# Voltage_Battery_Measure.net
KiCad netlist of a schematic drawn in Altium Designer
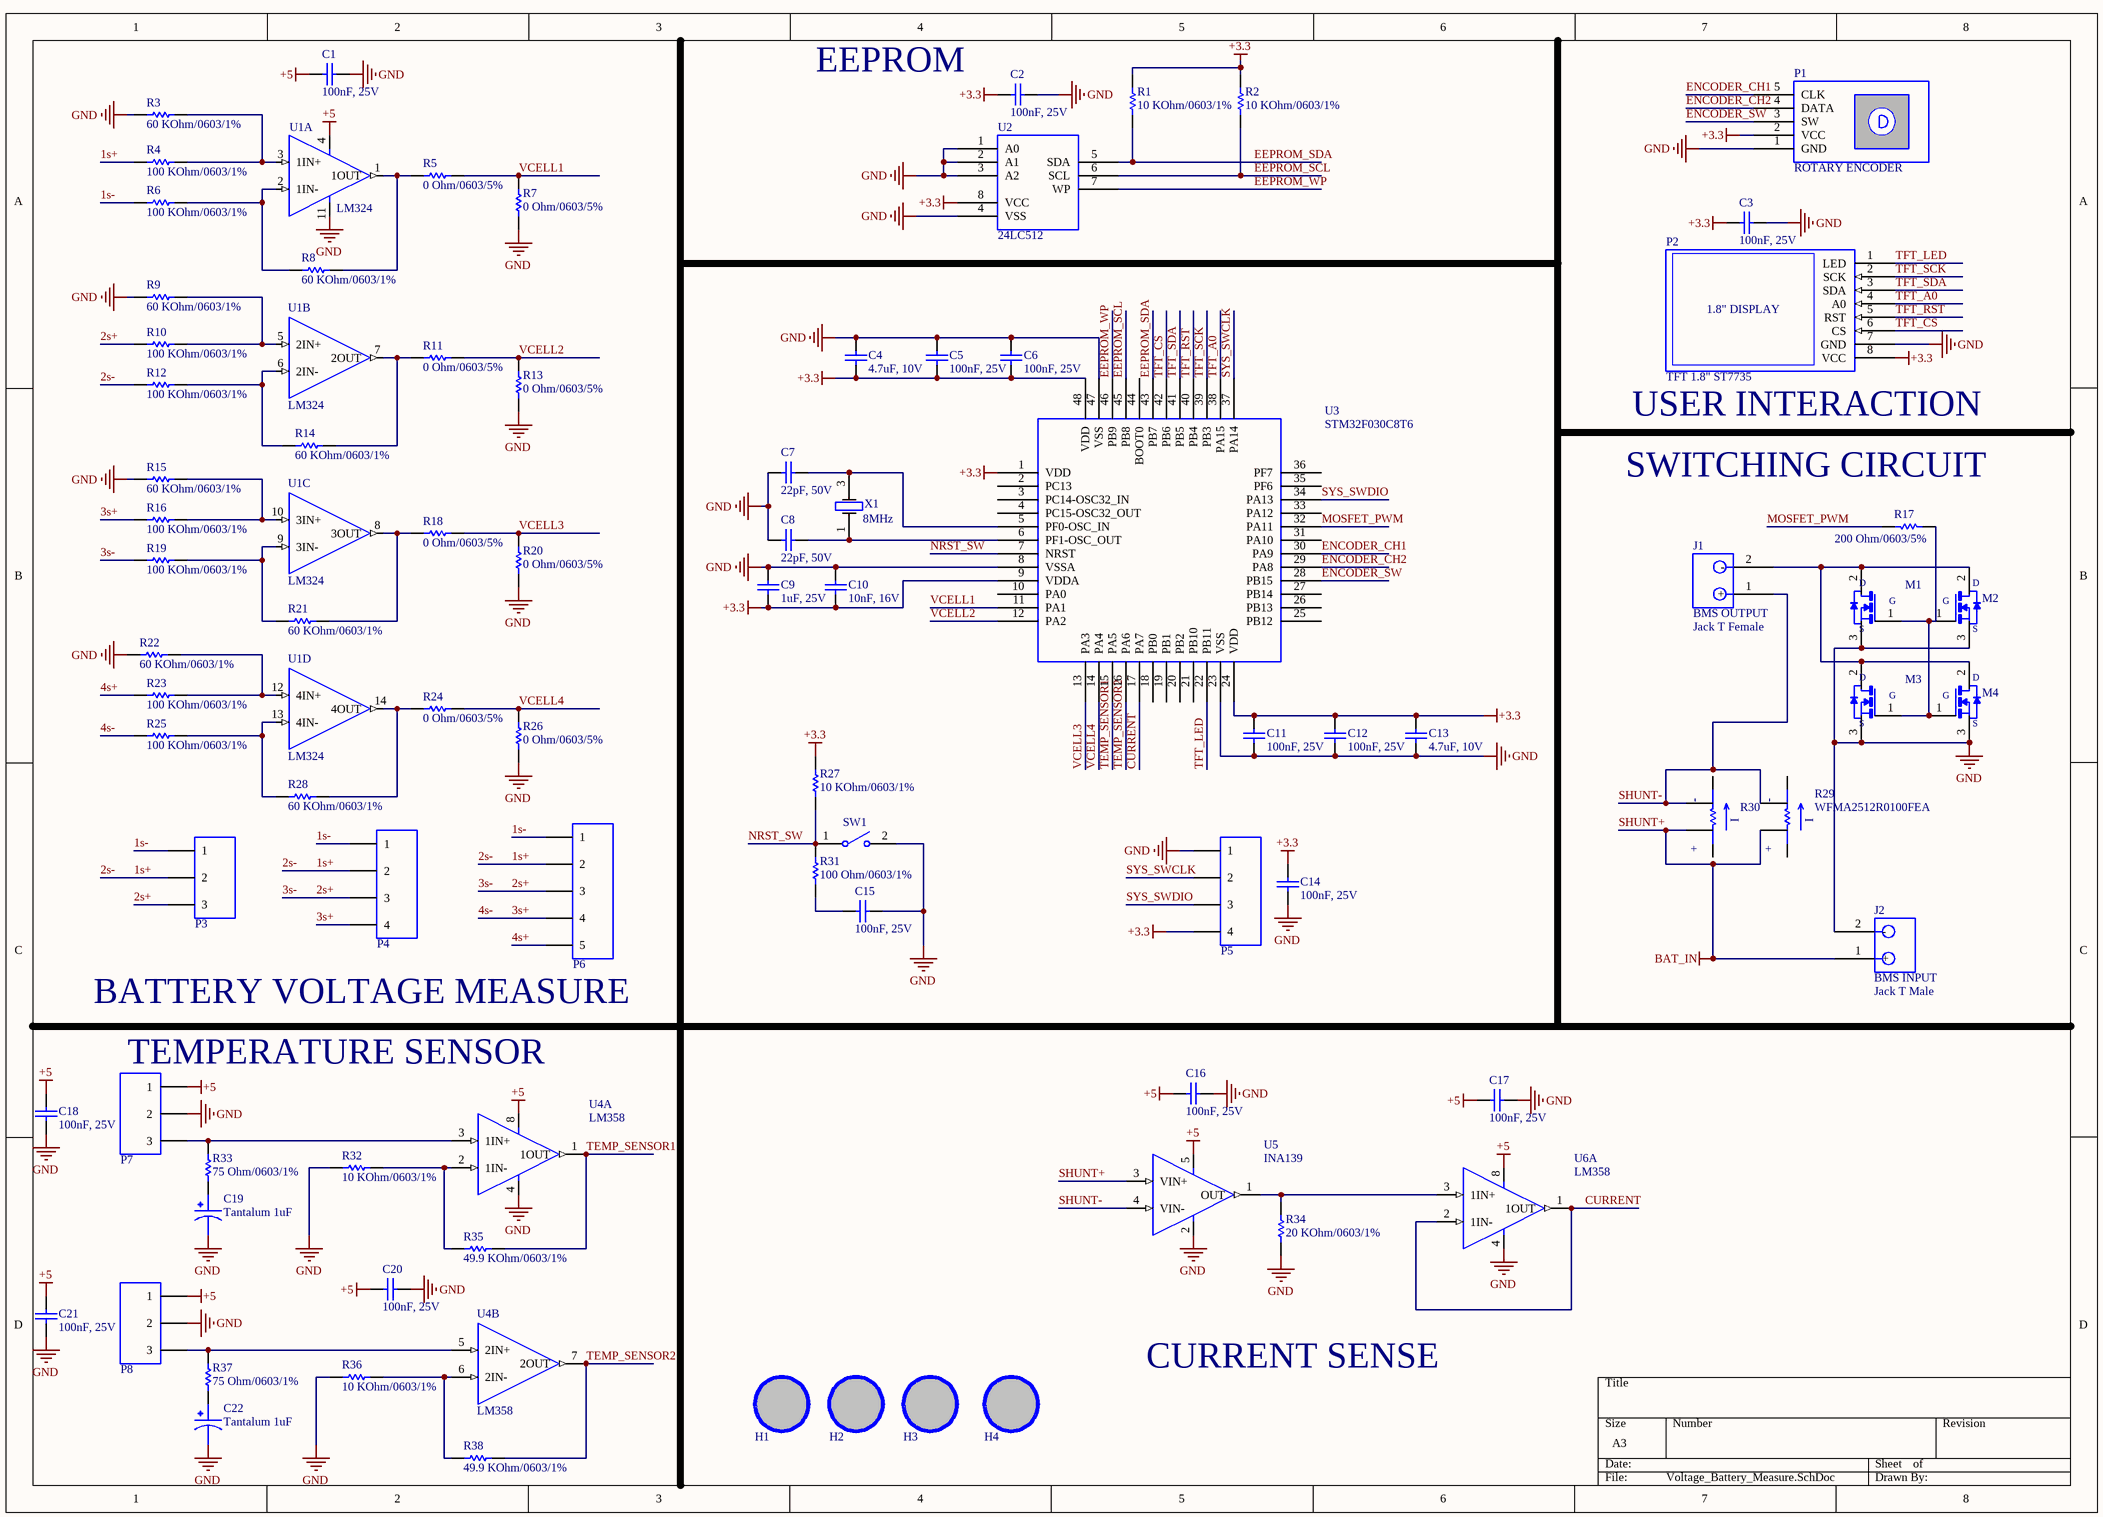
[diagram p0: Voltage_Battery_Measure.SchDoc]

(export (version "E")
  (design (tool "Eeschema 10.0.6"))
  (components
    (comp (ref "C1")
      (value "100nF, 25V")
      (footprint "WCAP-CSGP_0603_H=0.8mm_Reflow")
      (description "WCAP-CSGP Multilayer Ceramic Chip Capacitor, General Purpose, size 0603, X7R, 100nF, 25V")
      (fields
        (field (name "MANUFACTURER PART NUMBER") "885012206071")
        (field (name "MANUFACTURER") "Wurth Elektronik")
      )
      (libsource (lib "Altium_WCAP-CSGP (rev20a)") (part "885012206071"))
    )
    (comp (ref "C2")
      (value "100nF, 25V")
      (footprint "WCAP-CSGP_0603_H=0.8mm_Reflow")
      (description "WCAP-CSGP Multilayer Ceramic Chip Capacitor, General Purpose, size 0603, X7R, 100nF, 25V")
      (fields
        (field (name "MANUFACTURER PART NUMBER") "885012206071")
        (field (name "MANUFACTURER") "Wurth Elektronik")
      )
      (libsource (lib "Altium_WCAP-CSGP (rev20a)") (part "885012206071"))
    )
    (comp (ref "C3")
      (value "100nF, 25V")
      (footprint "WCAP-CSGP_0603_H=0.8mm_Reflow")
      (description "WCAP-CSGP Multilayer Ceramic Chip Capacitor, General Purpose, size 0603, X7R, 100nF, 25V")
      (fields
        (field (name "MANUFACTURER PART NUMBER") "885012206071")
        (field (name "MANUFACTURER") "Wurth Elektronik")
      )
      (libsource (lib "Altium_WCAP-CSGP (rev20a)") (part "885012206071"))
    )
    (comp (ref "C4")
      (value "4.7uF, 10V")
      (footprint "WCAP-CSGP_0603_H=0.8mm_Reflow")
      (description "WCAP-CSGP Multilayer Ceramic Chip Capacitor, General Purpose, size 0603, X5R, 4.7uF, 10V")
      (fields
        (field (name "MANUFACTURER PART NUMBER") "885012106012")
        (field (name "MANUFACTURER") "Wurth Elektronik")
      )
      (libsource (lib "Altium_WCAP-CSGP (rev20a)") (part "885012106012"))
    )
    (comp (ref "C5")
      (value "100nF, 25V")
      (footprint "WCAP-CSGP_0603_H=0.8mm_Reflow")
      (description "WCAP-CSGP Multilayer Ceramic Chip Capacitor, General Purpose, size 0603, X7R, 100nF, 25V")
      (fields
        (field (name "MANUFACTURER PART NUMBER") "885012206071")
        (field (name "MANUFACTURER") "Wurth Elektronik")
      )
      (libsource (lib "Altium_WCAP-CSGP (rev20a)") (part "885012206071"))
    )
    (comp (ref "C6")
      (value "100nF, 25V")
      (footprint "WCAP-CSGP_0603_H=0.8mm_Reflow")
      (description "WCAP-CSGP Multilayer Ceramic Chip Capacitor, General Purpose, size 0603, X7R, 100nF, 25V")
      (fields
        (field (name "MANUFACTURER PART NUMBER") "885012206071")
        (field (name "MANUFACTURER") "Wurth Elektronik")
      )
      (libsource (lib "Altium_WCAP-CSGP (rev20a)") (part "885012206071"))
    )
    (comp (ref "C7")
      (value "22pF, 50V")
      (footprint "WCAP-CSGP_0603_H=0.8mm_Reflow")
      (description "WCAP-CSGP Multilayer Ceramic Chip Capacitor, General Purpose, size 0603, NP0, 22pF, 50V")
      (fields
        (field (name "MANUFACTURER PART NUMBER") "885012006053")
        (field (name "MANUFACTURER") "Wurth Elektronik")
      )
      (libsource (lib "Altium_WCAP-CSGP (rev20a)") (part "885012006053"))
    )
    (comp (ref "C8")
      (value "22pF, 50V")
      (footprint "WCAP-CSGP_0603_H=0.8mm_Reflow")
      (description "WCAP-CSGP Multilayer Ceramic Chip Capacitor, General Purpose, size 0603, NP0, 22pF, 50V")
      (fields
        (field (name "MANUFACTURER PART NUMBER") "885012006053")
        (field (name "MANUFACTURER") "Wurth Elektronik")
      )
      (libsource (lib "Altium_WCAP-CSGP (rev20a)") (part "885012006053"))
    )
    (comp (ref "C9")
      (value "1uF, 25V")
      (footprint "WCAP-CSGP_0603_H=0.8mm_Reflow")
      (description "WCAP-CSGP Multilayer Ceramic Chip Capacitor, General Purpose, size 0603, X5R, 1uF, 25V")
      (fields
        (field (name "MANUFACTURER PART NUMBER") "885012106022")
        (field (name "MANUFACTURER") "Wurth Elektronik")
      )
      (libsource (lib "Altium_WCAP-CSGP (rev20a)") (part "885012106022"))
    )
    (comp (ref "C10")
      (value "10nF, 16V")
      (footprint "WCAP-CSGP_0603_H=0.8mm_Reflow")
      (description "WCAP-CSGP Multilayer Ceramic Chip Capacitor, General Purpose, size 0603, X7R, 10nF, 16V")
      (fields
        (field (name "MANUFACTURER PART NUMBER") "885012206040")
        (field (name "MANUFACTURER") "Wurth Elektronik")
      )
      (libsource (lib "Altium_WCAP-CSGP (rev20a)") (part "885012206040"))
    )
    (comp (ref "C11")
      (value "100nF, 25V")
      (footprint "WCAP-CSGP_0603_H=0.8mm_Reflow")
      (description "WCAP-CSGP Multilayer Ceramic Chip Capacitor, General Purpose, size 0603, X7R, 100nF, 25V")
      (fields
        (field (name "MANUFACTURER PART NUMBER") "885012206071")
        (field (name "MANUFACTURER") "Wurth Elektronik")
      )
      (libsource (lib "Altium_WCAP-CSGP (rev20a)") (part "885012206071"))
    )
    (comp (ref "C12")
      (value "100nF, 25V")
      (footprint "WCAP-CSGP_0603_H=0.8mm_Reflow")
      (description "WCAP-CSGP Multilayer Ceramic Chip Capacitor, General Purpose, size 0603, X7R, 100nF, 25V")
      (fields
        (field (name "MANUFACTURER PART NUMBER") "885012206071")
        (field (name "MANUFACTURER") "Wurth Elektronik")
      )
      (libsource (lib "Altium_WCAP-CSGP (rev20a)") (part "885012206071"))
    )
    (comp (ref "C13")
      (value "4.7uF, 10V")
      (footprint "WCAP-CSGP_0603_H=0.8mm_Reflow")
      (description "WCAP-CSGP Multilayer Ceramic Chip Capacitor, General Purpose, size 0603, X5R, 4.7uF, 10V")
      (fields
        (field (name "MANUFACTURER PART NUMBER") "885012106012")
        (field (name "MANUFACTURER") "Wurth Elektronik")
      )
      (libsource (lib "Altium_WCAP-CSGP (rev20a)") (part "885012106012"))
    )
    (comp (ref "C14")
      (value "100nF, 25V")
      (footprint "WCAP-CSGP_0603_H=0.8mm_Reflow")
      (description "WCAP-CSGP Multilayer Ceramic Chip Capacitor, General Purpose, size 0603, X7R, 100nF, 25V")
      (fields
        (field (name "MANUFACTURER PART NUMBER") "885012206071")
        (field (name "MANUFACTURER") "Wurth Elektronik")
      )
      (libsource (lib "Altium_WCAP-CSGP (rev20a)") (part "885012206071"))
    )
    (comp (ref "C15")
      (value "100nF, 25V")
      (footprint "WCAP-CSGP_0603_H=0.8mm_Reflow")
      (description "WCAP-CSGP Multilayer Ceramic Chip Capacitor, General Purpose, size 0603, X7R, 100nF, 25V")
      (fields
        (field (name "MANUFACTURER PART NUMBER") "885012206071")
        (field (name "MANUFACTURER") "Wurth Elektronik")
      )
      (libsource (lib "Altium_WCAP-CSGP (rev20a)") (part "885012206071"))
    )
    (comp (ref "C16")
      (value "100nF, 25V")
      (footprint "WCAP-CSGP_0603_H=0.8mm_Reflow")
      (description "WCAP-CSGP Multilayer Ceramic Chip Capacitor, General Purpose, size 0603, X7R, 100nF, 25V")
      (fields
        (field (name "MANUFACTURER PART NUMBER") "885012206071")
        (field (name "MANUFACTURER") "Wurth Elektronik")
      )
      (libsource (lib "Altium_WCAP-CSGP (rev20a)") (part "885012206071"))
    )
    (comp (ref "C17")
      (value "100nF, 25V")
      (footprint "WCAP-CSGP_0603_H=0.8mm_Reflow")
      (description "WCAP-CSGP Multilayer Ceramic Chip Capacitor, General Purpose, size 0603, X7R, 100nF, 25V")
      (fields
        (field (name "MANUFACTURER PART NUMBER") "885012206071")
        (field (name "MANUFACTURER") "Wurth Elektronik")
      )
      (libsource (lib "Altium_WCAP-CSGP (rev20a)") (part "885012206071"))
    )
    (comp (ref "C18")
      (value "100nF, 25V")
      (footprint "WCAP-CSGP_0603_H=0.8mm_Reflow")
      (description "WCAP-CSGP Multilayer Ceramic Chip Capacitor, General Purpose, size 0603, X7R, 100nF, 25V")
      (fields
        (field (name "MANUFACTURER PART NUMBER") "885012206071")
        (field (name "MANUFACTURER") "Wurth Elektronik")
      )
      (libsource (lib "Altium_WCAP-CSGP (rev20a)") (part "885012206071"))
    )
    (comp (ref "C19")
      (value "Tantalum 1uF")
      (footprint "C1206")
      (description "Code 105 10%, 1206 (3216 Metric)")
      (fields (field (name "MF") "AVX") (field (name "MP") "TAJC226K016RNJ"))
      (libsource (lib "Giang's Libs") (part "Tantalum Capacitor"))
    )
    (comp (ref "C20")
      (value "100nF, 25V")
      (footprint "WCAP-CSGP_0603_H=0.8mm_Reflow")
      (description "WCAP-CSGP Multilayer Ceramic Chip Capacitor, General Purpose, size 0603, X7R, 100nF, 25V")
      (fields
        (field (name "MANUFACTURER PART NUMBER") "885012206071")
        (field (name "MANUFACTURER") "Wurth Elektronik")
      )
      (libsource (lib "Altium_WCAP-CSGP (rev20a)") (part "885012206071"))
    )
    (comp (ref "C21")
      (value "100nF, 25V")
      (footprint "WCAP-CSGP_0603_H=0.8mm_Reflow")
      (description "WCAP-CSGP Multilayer Ceramic Chip Capacitor, General Purpose, size 0603, X7R, 100nF, 25V")
      (fields
        (field (name "MANUFACTURER PART NUMBER") "885012206071")
        (field (name "MANUFACTURER") "Wurth Elektronik")
      )
      (libsource (lib "Altium_WCAP-CSGP (rev20a)") (part "885012206071"))
    )
    (comp (ref "C22")
      (value "Tantalum 1uF")
      (footprint "C1206")
      (description "Code 105 10%, 1206 (3216 Metric)")
      (fields (field (name "MF") "AVX") (field (name "MP") "TAJC226K016RNJ"))
      (libsource (lib "Giang's Libs") (part "Tantalum Capacitor"))
    )
    (comp (ref "H1")
      (value "Hole")
      (footprint "LO KHOAN 3MM")
      (description "Hole 3mm")
      (libsource (lib "PIF_Library") (part "Hole"))
    )
    (comp (ref "H2")
      (value "Hole")
      (footprint "LO KHOAN 3MM")
      (description "Hole 3mm")
      (libsource (lib "PIF_Library") (part "Hole"))
    )
    (comp (ref "H3")
      (value "Hole")
      (footprint "LO KHOAN 3MM")
      (description "Hole 3mm")
      (libsource (lib "PIF_Library") (part "Hole"))
    )
    (comp (ref "H4")
      (value "Hole")
      (footprint "LO KHOAN 3MM")
      (description "Hole 3mm")
      (libsource (lib "PIF_Library") (part "Hole"))
    )
    (comp (ref "J1")
      (value "BMS OUTPUT")
      (footprint "Jack T - FEMALE")
      (description "Jack T 120A")
      (fields (field (name "ALTIUM_VALUE") "Jack T Female"))
      (libsource (lib "Giang's Libs") (part "Jack T Female"))
    )
    (comp (ref "J2")
      (value "BMS INPUT")
      (footprint "Jack T - Male")
      (description "Jack T 120A")
      (fields (field (name "ALTIUM_VALUE") "Jack T Male"))
      (libsource (lib "Giang's Libs") (part "Jack T Male"))
    )
    (comp (ref "M1")
      (value "AOD472")
      (footprint "TO252-3")
      (description "MOSFET 25V 55A N-Channel")
      (libsource (lib "Giang_Transistor") (part "AOD472"))
    )
    (comp (ref "M2")
      (value "AOD472")
      (footprint "TO252-3")
      (description "MOSFET 25V 55A N-Channel")
      (libsource (lib "") (part "AOD472_1"))
    )
    (comp (ref "M3")
      (value "AOD472")
      (footprint "TO252-3")
      (description "MOSFET 25V 55A N-Channel")
      (libsource (lib "Giang_Transistor") (part "AOD472"))
    )
    (comp (ref "M4")
      (value "AOD472")
      (footprint "TO252-3")
      (description "MOSFET 25V 55A N-Channel")
      (libsource (lib "") (part "AOD472_1"))
    )
    (comp (ref "P1")
      (value "ROTARY ENCODER")
      (footprint "Rotary Encoder")
      (description "KY-040")
      (fields (field (name "Comment") "Rotary Encoder"))
      (libsource (lib "Giang's Libs") (part "MODULE ROTARY ENCODER"))
    )
    (comp (ref "P2")
      (value "TFT 1.8\" ST7735")
      (footprint "JP8")
      (description "LCD 1.8inch 160x128 TFT ST7735")
      (libsource (lib "Giang's Libs") (part "TFT 1.8{dblquote} ST7735"))
    )
    (comp (ref "P3")
      (value "Header 3H")
      (footprint "JP3H")
      (description "Header, 3-Pin, Right Angle")
      (fields (field (name "PUBLISHER") "Altium Limited"))
      (libsource (lib "") (part "Header 3H_1"))
    )
    (comp (ref "P4")
      (value "Header 4H")
      (footprint "JP4H")
      (description "Header, 4-Pin, Right Angle")
      (fields (field (name "PUBLISHER") "Altium Limited"))
      (libsource (lib "PIF_Library") (part "Header 4H"))
    )
    (comp (ref "P5")
      (value "Header 4H")
      (footprint "JP4H")
      (description "Header, 4-Pin, Right Angle")
      (fields (field (name "PUBLISHER") "Altium Limited"))
      (libsource (lib "PIF_Library") (part "Header 4H"))
    )
    (comp (ref "P6")
      (value "Header 5H")
      (footprint "JP5H")
      (description "Header, 5-Pin, Right Angle")
      (fields (field (name "PUBLISHER") "Altium Limited"))
      (libsource (lib "PIF_Library") (part "Header 5H"))
    )
    (comp (ref "P7")
      (value "Header 3H")
      (footprint "JP3H")
      (description "Header, 3-Pin, Right Angle")
      (fields (field (name "PUBLISHER") "Altium Limited"))
      (libsource (lib "PIF_Library") (part "Header 3H"))
    )
    (comp (ref "P8")
      (value "Header 3H")
      (footprint "JP3H")
      (description "Header, 3-Pin, Right Angle")
      (fields (field (name "PUBLISHER") "Altium Limited"))
      (libsource (lib "PIF_Library") (part "Header 3H"))
    )
    (comp (ref "R1")
      (value "10 KOhm/0603/1%")
      (footprint "R0603")
      (description "Code 103, 1/10W")
      (fields (field (name "Comment") "Resistor 10 KOhm 0603 1%"))
      (libsource (lib "Giang_Resistor") (part "Resistor 10 KOhm 0603 1%"))
    )
    (comp (ref "R2")
      (value "10 KOhm/0603/1%")
      (footprint "R0603")
      (description "Code 103, 1/10W")
      (fields (field (name "Comment") "Resistor 10 KOhm 0603 1%"))
      (libsource (lib "Giang_Resistor") (part "Resistor 10 KOhm 0603 1%"))
    )
    (comp (ref "R3")
      (value "60 KOhm/0603/1%")
      (footprint "R0603")
      (description "Code 603, 1/10W")
      (fields (field (name "Comment") "Resistor 60 KOhm 0603 1%"))
      (libsource (lib "Giang_Resistor") (part "Resistor 60 KOhm 0603 1%"))
    )
    (comp (ref "R4")
      (value "100 KOhm/0603/1%")
      (footprint "R0603")
      (description "Code 104, 1/10W")
      (fields (field (name "Comment") "Resistor 100 KOhm 0603 1%"))
      (libsource (lib "Giang_Resistor") (part "Resistor 100 KOhm 0603 1%"))
    )
    (comp (ref "R5")
      (value "0 Ohm/0603/5%")
      (footprint "R0603")
      (description "Code 0R, 1/10W")
      (fields (field (name "Comment") "Resistor 0 Ohm 0603 5%"))
      (libsource (lib "Giang_Resistor") (part "Resistor 0 Ohm 0603 5%"))
    )
    (comp (ref "R6")
      (value "100 KOhm/0603/1%")
      (footprint "R0603")
      (description "Code 104, 1/10W")
      (fields (field (name "Comment") "Resistor 100 KOhm 0603 1%"))
      (libsource (lib "Giang_Resistor") (part "Resistor 100 KOhm 0603 1%"))
    )
    (comp (ref "R7")
      (value "0 Ohm/0603/5%")
      (footprint "R0603")
      (description "Code 0R, 1/10W")
      (fields (field (name "Comment") "Resistor 0 Ohm 0603 5%"))
      (libsource (lib "Giang_Resistor") (part "Resistor 0 Ohm 0603 5%"))
    )
    (comp (ref "R8")
      (value "60 KOhm/0603/1%")
      (footprint "R0603")
      (description "Code 603, 1/10W")
      (fields (field (name "Comment") "Resistor 60 KOhm 0603 1%"))
      (libsource (lib "Giang_Resistor") (part "Resistor 60 KOhm 0603 1%"))
    )
    (comp (ref "R9")
      (value "60 KOhm/0603/1%")
      (footprint "R0603")
      (description "Code 603, 1/10W")
      (fields (field (name "Comment") "Resistor 60 KOhm 0603 1%"))
      (libsource (lib "Giang_Resistor") (part "Resistor 60 KOhm 0603 1%"))
    )
    (comp (ref "R10")
      (value "100 KOhm/0603/1%")
      (footprint "R0603")
      (description "Code 104, 1/10W")
      (fields (field (name "Comment") "Resistor 100 KOhm 0603 1%"))
      (libsource (lib "Giang_Resistor") (part "Resistor 100 KOhm 0603 1%"))
    )
    (comp (ref "R11")
      (value "0 Ohm/0603/5%")
      (footprint "R0603")
      (description "Code 0R, 1/10W")
      (fields (field (name "Comment") "Resistor 0 Ohm 0603 5%"))
      (libsource (lib "Giang_Resistor") (part "Resistor 0 Ohm 0603 5%"))
    )
    (comp (ref "R12")
      (value "100 KOhm/0603/1%")
      (footprint "R0603")
      (description "Code 104, 1/10W")
      (fields (field (name "Comment") "Resistor 100 KOhm 0603 1%"))
      (libsource (lib "Giang_Resistor") (part "Resistor 100 KOhm 0603 1%"))
    )
    (comp (ref "R13")
      (value "0 Ohm/0603/5%")
      (footprint "R0603")
      (description "Code 0R, 1/10W")
      (fields (field (name "Comment") "Resistor 0 Ohm 0603 5%"))
      (libsource (lib "Giang_Resistor") (part "Resistor 0 Ohm 0603 5%"))
    )
    (comp (ref "R14")
      (value "60 KOhm/0603/1%")
      (footprint "R0603")
      (description "Code 603, 1/10W")
      (fields (field (name "Comment") "Resistor 60 KOhm 0603 1%"))
      (libsource (lib "Giang_Resistor") (part "Resistor 60 KOhm 0603 1%"))
    )
    (comp (ref "R15")
      (value "60 KOhm/0603/1%")
      (footprint "R0603")
      (description "Code 603, 1/10W")
      (fields (field (name "Comment") "Resistor 60 KOhm 0603 1%"))
      (libsource (lib "Giang_Resistor") (part "Resistor 60 KOhm 0603 1%"))
    )
    (comp (ref "R16")
      (value "100 KOhm/0603/1%")
      (footprint "R0603")
      (description "Code 104, 1/10W")
      (fields (field (name "Comment") "Resistor 100 KOhm 0603 1%"))
      (libsource (lib "Giang_Resistor") (part "Resistor 100 KOhm 0603 1%"))
    )
    (comp (ref "R17")
      (value "200 Ohm/0603/5%")
      (footprint "R0603")
      (description "Code 201, 1/10W")
      (fields (field (name "Comment") "Resistor 200 Ohm 0603 5%"))
      (libsource (lib "Giang_Resistor") (part "Resistor 200 Ohm 0603 5%"))
    )
    (comp (ref "R18")
      (value "0 Ohm/0603/5%")
      (footprint "R0603")
      (description "Code 0R, 1/10W")
      (fields (field (name "Comment") "Resistor 0 Ohm 0603 5%"))
      (libsource (lib "Giang_Resistor") (part "Resistor 0 Ohm 0603 5%"))
    )
    (comp (ref "R19")
      (value "100 KOhm/0603/1%")
      (footprint "R0603")
      (description "Code 104, 1/10W")
      (fields (field (name "Comment") "Resistor 100 KOhm 0603 1%"))
      (libsource (lib "Giang_Resistor") (part "Resistor 100 KOhm 0603 1%"))
    )
    (comp (ref "R20")
      (value "0 Ohm/0603/5%")
      (footprint "R0603")
      (description "Code 0R, 1/10W")
      (fields (field (name "Comment") "Resistor 0 Ohm 0603 5%"))
      (libsource (lib "Giang_Resistor") (part "Resistor 0 Ohm 0603 5%"))
    )
    (comp (ref "R21")
      (value "60 KOhm/0603/1%")
      (footprint "R0603")
      (description "Code 603, 1/10W")
      (fields (field (name "Comment") "Resistor 60 KOhm 0603 1%"))
      (libsource (lib "Giang_Resistor") (part "Resistor 60 KOhm 0603 1%"))
    )
    (comp (ref "R22")
      (value "60 KOhm/0603/1%")
      (footprint "R0603")
      (description "Code 603, 1/10W")
      (fields (field (name "Comment") "Resistor 60 KOhm 0603 1%"))
      (libsource (lib "Giang_Resistor") (part "Resistor 60 KOhm 0603 1%"))
    )
    (comp (ref "R23")
      (value "100 KOhm/0603/1%")
      (footprint "R0603")
      (description "Code 104, 1/10W")
      (fields (field (name "Comment") "Resistor 100 KOhm 0603 1%"))
      (libsource (lib "Giang_Resistor") (part "Resistor 100 KOhm 0603 1%"))
    )
    (comp (ref "R24")
      (value "0 Ohm/0603/5%")
      (footprint "R0603")
      (description "Code 0R, 1/10W")
      (fields (field (name "Comment") "Resistor 0 Ohm 0603 5%"))
      (libsource (lib "Giang_Resistor") (part "Resistor 0 Ohm 0603 5%"))
    )
    (comp (ref "R25")
      (value "100 KOhm/0603/1%")
      (footprint "R0603")
      (description "Code 104, 1/10W")
      (fields (field (name "Comment") "Resistor 100 KOhm 0603 1%"))
      (libsource (lib "Giang_Resistor") (part "Resistor 100 KOhm 0603 1%"))
    )
    (comp (ref "R26")
      (value "0 Ohm/0603/5%")
      (footprint "R0603")
      (description "Code 0R, 1/10W")
      (fields (field (name "Comment") "Resistor 0 Ohm 0603 5%"))
      (libsource (lib "Giang_Resistor") (part "Resistor 0 Ohm 0603 5%"))
    )
    (comp (ref "R27")
      (value "10 KOhm/0603/1%")
      (footprint "R0603")
      (description "Code 103, 1/10W")
      (fields (field (name "Comment") "Resistor 10 KOhm 0603 1%"))
      (libsource (lib "Giang_Resistor") (part "Resistor 10 KOhm 0603 1%"))
    )
    (comp (ref "R28")
      (value "60 KOhm/0603/1%")
      (footprint "R0603")
      (description "Code 603, 1/10W")
      (fields (field (name "Comment") "Resistor 60 KOhm 0603 1%"))
      (libsource (lib "Giang_Resistor") (part "Resistor 60 KOhm 0603 1%"))
    )
    (comp (ref "R29")
      (value "WFMA2512R0100FEA")
      (footprint "R2512")
      (description "Shunt Resistor")
      (fields (field (name "Comment") "Current Sense Resistor"))
      (libsource (lib "Giang_Resistor") (part "Current Sense Resistor"))
    )
    (comp (ref "R30")
      (value "Current Sense Resistor")
      (footprint "R2512")
      (description "Shunt Resistor")
      (libsource (lib "Giang_Resistor") (part "Current Sense Resistor"))
    )
    (comp (ref "R31")
      (value "100 Ohm/0603/1%")
      (footprint "R0603")
      (description "Code 1000, 1/10W")
      (fields (field (name "Comment") "Resistor 100 Ohm 0603 1%"))
      (libsource (lib "Giang_Resistor") (part "Resistor 100 Ohm 0603 1%"))
    )
    (comp (ref "R32")
      (value "10 KOhm/0603/1%")
      (footprint "R0603")
      (description "Code 103, 1/10W")
      (fields (field (name "Comment") "Resistor 10 KOhm 0603 1%"))
      (libsource (lib "Giang_Resistor") (part "Resistor 10 KOhm 0603 1%"))
    )
    (comp (ref "R33")
      (value "75 Ohm/0603/1%")
      (footprint "R0603")
      (description "Code 750, 1/10W")
      (fields (field (name "Comment") "Resistor 75 Ohm 0603 1%"))
      (libsource (lib "Giang_Resistor") (part "Resistor 75 Ohm 0603 1%"))
    )
    (comp (ref "R34")
      (value "20 KOhm/0603/1%")
      (footprint "R0603")
      (description "Code 203,1/10W")
      (fields (field (name "Comment") "Resistor 20 KOhm 0603 1%"))
      (libsource (lib "Giang_Resistor") (part "Resistor 20 KOhm 0603 1%"))
    )
    (comp (ref "R35")
      (value "49.9 KOhm/0603/1%")
      (footprint "R0603")
      (description "Code (4992, 68C), 1/10W")
      (fields (field (name "Comment") "Resistor 49.9 KOhm 0603 1%"))
      (libsource (lib "Giang_Resistor") (part "Resistor 49.9 KOhm 0603 1%"))
    )
    (comp (ref "R36")
      (value "10 KOhm/0603/1%")
      (footprint "R0603")
      (description "Code 103, 1/10W")
      (fields (field (name "Comment") "Resistor 10 KOhm 0603 1%"))
      (libsource (lib "Giang_Resistor") (part "Resistor 10 KOhm 0603 1%"))
    )
    (comp (ref "R37")
      (value "75 Ohm/0603/1%")
      (footprint "R0603")
      (description "Code 750, 1/10W")
      (fields (field (name "Comment") "Resistor 75 Ohm 0603 1%"))
      (libsource (lib "Giang_Resistor") (part "Resistor 75 Ohm 0603 1%"))
    )
    (comp (ref "R38")
      (value "49.9 KOhm/0603/1%")
      (footprint "R0603")
      (description "Code (4992, 68C), 1/10W")
      (fields (field (name "Comment") "Resistor 49.9 KOhm 0603 1%"))
      (libsource (lib "Giang_Resistor") (part "Resistor 49.9 KOhm 0603 1%"))
    )
    (comp (ref "SW1")
      (value "434123050816")
      (footprint "WS-TASV_L6W3.5H5_4341x30508x6")
      (description "WS-TASV J-Bend SMT Tact Switch, 12VDC, 50mA, 160g, height 5mm")
      (fields (field (name "MANUFACTURER") "Wurth Elektronik"))
      (libsource (lib "Altium_WS-TASV (rev22a)") (part "434123050816"))
    )
    (comp (ref "U1")
      (value "LM324")
      (footprint "SOIC-14")
      (description "OPAMP General Purpose Amplifier 4 Circuit 1.2MHz")
      (libsource (lib "Giang_OPAMP") (part "LM324"))
    )
    (comp (ref "U2")
      (value "24LC512")
      (footprint "SOIC-8")
      (description "EEPROM")
      (fields (field (name "Comment") "24LCxx"))
      (libsource (lib "Giang's Libs") (part "24LCxx"))
    )
    (comp (ref "U3")
      (value "STM32F030C8T6")
      (footprint "48-LQFP")
      (libsource (lib "Giang_MCU") (part "STM32F030C8T6"))
    )
    (comp (ref "U4")
      (value "LM358")
      (footprint "SOIC-8")
      (description "General Purpose Amplifier 2 Circuit 1.1MHz")
      (libsource (lib "Giang_OPAMP") (part "LM358"))
    )
    (comp (ref "U5")
      (value "INA139")
      (footprint "SOT-23")
      (description "High-Side Measurement Current Shunt Monitor")
      (libsource (lib "Giang_OPAMP") (part "INA139"))
    )
    (comp (ref "U6")
      (value "LM358")
      (footprint "SOIC-8")
      (description "General Purpose Amplifier 2 Circuit 1.1MHz")
      (libsource (lib "Giang_OPAMP") (part "LM358"))
    )
    (comp (ref "X1")
      (value "8MHz")
      (footprint "XTAL 3225")
      (fields (field (name "Comment") "XTAL"))
      (libsource (lib "MiclsLib") (part "XTAL"))
    )
  )
  (nets
    (net (code "1") (name "+3.3") (class "Default")
      (node (ref "C10") (pin "1") (pinfunction "1_1") (pintype "passive"))
      (node (ref "C11") (pin "2") (pinfunction "2_2") (pintype "passive"))
      (node (ref "C12") (pin "2") (pinfunction "2_2") (pintype "passive"))
      (node (ref "C13") (pin "2") (pinfunction "2_2") (pintype "passive"))
      (node (ref "C14") (pin "2") (pinfunction "2_2") (pintype "passive"))
      (node (ref "C2") (pin "2") (pinfunction "2_2") (pintype "passive"))
      (node (ref "C3") (pin "2") (pinfunction "2_2") (pintype "passive"))
      (node (ref "C4") (pin "1") (pinfunction "1_1") (pintype "passive"))
      (node (ref "C5") (pin "1") (pinfunction "1_1") (pintype "passive"))
      (node (ref "C6") (pin "1") (pinfunction "1_1") (pintype "passive"))
      (node (ref "C9") (pin "1") (pinfunction "1_1") (pintype "passive"))
      (node (ref "P1") (pin "2") (pinfunction "VCC_2") (pintype "passive"))
      (node (ref "P2") (pin "8") (pinfunction "VCC_8") (pintype "power_in"))
      (node (ref "P5") (pin "4") (pinfunction "4_4") (pintype "passive"))
      (node (ref "R1") (pin "2") (pinfunction "2_2") (pintype "passive"))
      (node (ref "R2") (pin "2") (pinfunction "2_2") (pintype "passive"))
      (node (ref "R27") (pin "2") (pinfunction "2_2") (pintype "passive"))
      (node (ref "U2") (pin "8") (pinfunction "VCC_8") (pintype "passive"))
      (node (ref "U3") (pin "1") (pinfunction "VDD_1") (pintype "passive"))
      (node (ref "U3") (pin "24") (pinfunction "VDD_24") (pintype "passive"))
      (node (ref "U3") (pin "48") (pinfunction "VDD_48") (pintype "passive"))
      (node (ref "U3") (pin "9") (pinfunction "VDDA_9") (pintype "passive"))
    )
    (net (code "2") (name "+5") (class "Default")
      (node (ref "C1") (pin "2") (pinfunction "2_2") (pintype "passive"))
      (node (ref "C16") (pin "2") (pinfunction "2_2") (pintype "passive"))
      (node (ref "C17") (pin "2") (pinfunction "2_2") (pintype "passive"))
      (node (ref "C18") (pin "2") (pinfunction "2_2") (pintype "passive"))
      (node (ref "C20") (pin "2") (pinfunction "2_2") (pintype "passive"))
      (node (ref "C21") (pin "2") (pinfunction "2_2") (pintype "passive"))
      (node (ref "P7") (pin "1") (pinfunction "1_1") (pintype "passive"))
      (node (ref "P8") (pin "1") (pinfunction "1_1") (pintype "passive"))
      (node (ref "U1") (pin "4") (pinfunction "VCC+_4") (pintype "power_in"))
      (node (ref "U4") (pin "8") (pinfunction "VCC+_8") (pintype "power_in"))
      (node (ref "U5") (pin "5") (pinfunction "VCC+_5") (pintype "power_in"))
      (node (ref "U6") (pin "8") (pinfunction "VCC+_8") (pintype "power_in"))
    )
    (net (code "3") (name "/1s+") (class "Default")
      (node (ref "P3") (pin "2") (pinfunction "2_2") (pintype "passive"))
      (node (ref "P4") (pin "2") (pinfunction "2_2") (pintype "passive"))
      (node (ref "P6") (pin "2") (pinfunction "2_2") (pintype "passive"))
      (node (ref "R12") (pin "1") (pinfunction "1_1") (pintype "passive"))
      (node (ref "R4") (pin "1") (pinfunction "1_1") (pintype "passive"))
    )
    (net (code "4") (name "/1s-") (class "Default")
      (node (ref "P3") (pin "1") (pinfunction "1_1") (pintype "passive"))
      (node (ref "P4") (pin "1") (pinfunction "1_1") (pintype "passive"))
      (node (ref "P6") (pin "1") (pinfunction "1_1") (pintype "passive"))
      (node (ref "R6") (pin "1") (pinfunction "1_1") (pintype "passive"))
    )
    (net (code "5") (name "/2s+") (class "Default")
      (node (ref "P3") (pin "3") (pinfunction "3_3") (pintype "passive"))
      (node (ref "P4") (pin "3") (pinfunction "3_3") (pintype "passive"))
      (node (ref "P6") (pin "3") (pinfunction "3_3") (pintype "passive"))
      (node (ref "R10") (pin "1") (pinfunction "1_1") (pintype "passive"))
      (node (ref "R19") (pin "1") (pinfunction "1_1") (pintype "passive"))
    )
    (net (code "6") (name "/3s+") (class "Default")
      (node (ref "P4") (pin "4") (pinfunction "4_4") (pintype "passive"))
      (node (ref "P6") (pin "4") (pinfunction "4_4") (pintype "passive"))
      (node (ref "R16") (pin "1") (pinfunction "1_1") (pintype "passive"))
      (node (ref "R25") (pin "1") (pinfunction "1_1") (pintype "passive"))
    )
    (net (code "7") (name "/4s+") (class "Default")
      (node (ref "P6") (pin "5") (pinfunction "5_5") (pintype "passive"))
      (node (ref "R23") (pin "1") (pinfunction "1_1") (pintype "passive"))
    )
    (net (code "8") (name "/CURRENT") (class "Default")
      (node (ref "U3") (pin "17") (pinfunction "PA7_17") (pintype "passive"))
      (node (ref "U6") (pin "1") (pinfunction "1OUT_1") (pintype "output"))
      (node (ref "U6") (pin "2") (pinfunction "1IN-_2") (pintype "input"))
    )
    (net (code "9") (name "/EEPROM_SCL") (class "Default")
      (node (ref "R2") (pin "1") (pinfunction "1_1") (pintype "passive"))
      (node (ref "U2") (pin "6") (pinfunction "SCL_6") (pintype "passive"))
      (node (ref "U3") (pin "45") (pinfunction "PB8_45") (pintype "passive"))
    )
    (net (code "10") (name "/EEPROM_SDA") (class "Default")
      (node (ref "R1") (pin "1") (pinfunction "1_1") (pintype "passive"))
      (node (ref "U2") (pin "5") (pinfunction "SDA_5") (pintype "passive"))
      (node (ref "U3") (pin "43") (pinfunction "PB7_43") (pintype "passive"))
    )
    (net (code "11") (name "/EEPROM_WP") (class "Default")
      (node (ref "U2") (pin "7") (pinfunction "WP_7") (pintype "passive"))
      (node (ref "U3") (pin "46") (pinfunction "PB9_46") (pintype "passive"))
    )
    (net (code "12") (name "/ENCODER_CH1") (class "Default")
      (node (ref "P1") (pin "5") (pinfunction "CLK_5") (pintype "passive"))
      (node (ref "U3") (pin "30") (pinfunction "PA9_30") (pintype "passive"))
    )
    (net (code "13") (name "/ENCODER_CH2") (class "Default")
      (node (ref "P1") (pin "4") (pinfunction "DATA_4") (pintype "passive"))
      (node (ref "U3") (pin "29") (pinfunction "PA8_29") (pintype "passive"))
    )
    (net (code "14") (name "/ENCODER_SW") (class "Default")
      (node (ref "P1") (pin "3") (pinfunction "SW_3") (pintype "passive"))
      (node (ref "U3") (pin "28") (pinfunction "PB15_28") (pintype "passive"))
    )
    (net (code "15") (name "/MOSFET_PWM") (class "Default")
      (node (ref "R17") (pin "2") (pinfunction "2_2") (pintype "passive"))
      (node (ref "U3") (pin "32") (pinfunction "PA11_32") (pintype "passive"))
    )
    (net (code "16") (name "/NRST_SW") (class "Default")
      (node (ref "R27") (pin "1") (pinfunction "1_1") (pintype "passive"))
      (node (ref "R31") (pin "2") (pinfunction "2_2") (pintype "passive"))
      (node (ref "SW1") (pin "1") (pinfunction "1_1") (pintype "passive"))
      (node (ref "U3") (pin "7") (pinfunction "NRST_7") (pintype "passive"))
    )
    (net (code "17") (name "/SHUNT-") (class "Default")
      (node (ref "J1") (pin "1") (pinfunction "+_1") (pintype "power_in"))
      (node (ref "R29") (pin "2") (pinfunction "-_2") (pintype "passive"))
      (node (ref "R30") (pin "2") (pinfunction "-_2") (pintype "passive"))
      (node (ref "U5") (pin "4") (pinfunction "VIN-_4") (pintype "input"))
    )
    (net (code "18") (name "/SYS_SWCLK") (class "Default")
      (node (ref "P5") (pin "2") (pinfunction "2_2") (pintype "passive"))
      (node (ref "U3") (pin "37") (pinfunction "PA14_37") (pintype "passive"))
    )
    (net (code "19") (name "/SYS_SWDIO") (class "Default")
      (node (ref "P5") (pin "3") (pinfunction "3_3") (pintype "passive"))
      (node (ref "U3") (pin "34") (pinfunction "PA13_34") (pintype "passive"))
    )
    (net (code "20") (name "/TEMP_SENSOR1") (class "Default")
      (node (ref "R35") (pin "2") (pinfunction "2_2") (pintype "passive"))
      (node (ref "U3") (pin "15") (pinfunction "PA5_15") (pintype "passive"))
      (node (ref "U4") (pin "1") (pinfunction "1OUT_1") (pintype "output"))
    )
    (net (code "21") (name "/TEMP_SENSOR2") (class "Default")
      (node (ref "R38") (pin "2") (pinfunction "2_2") (pintype "passive"))
      (node (ref "U3") (pin "16") (pinfunction "PA6_16") (pintype "passive"))
      (node (ref "U4") (pin "7") (pinfunction "2OUT_7") (pintype "output"))
    )
    (net (code "22") (name "/TFT_A0") (class "Default")
      (node (ref "P2") (pin "4") (pinfunction "A0_4") (pintype "input"))
      (node (ref "U3") (pin "38") (pinfunction "PA15_38") (pintype "passive"))
    )
    (net (code "23") (name "/TFT_CS") (class "Default")
      (node (ref "P2") (pin "6") (pinfunction "CS_6") (pintype "input"))
      (node (ref "U3") (pin "42") (pinfunction "PB6_42") (pintype "passive"))
    )
    (net (code "24") (name "/TFT_LED") (class "Default")
      (node (ref "P2") (pin "1") (pinfunction "LED_1") (pintype "power_in"))
      (node (ref "U3") (pin "22") (pinfunction "PB11_22") (pintype "passive"))
    )
    (net (code "25") (name "/TFT_RST") (class "Default")
      (node (ref "P2") (pin "5") (pinfunction "RST_5") (pintype "input"))
      (node (ref "U3") (pin "40") (pinfunction "PB4_40") (pintype "passive"))
    )
    (net (code "26") (name "/TFT_SCK") (class "Default")
      (node (ref "P2") (pin "2") (pinfunction "SCK_2") (pintype "input"))
      (node (ref "U3") (pin "39") (pinfunction "PB3_39") (pintype "passive"))
    )
    (net (code "27") (name "/TFT_SDA") (class "Default")
      (node (ref "P2") (pin "3") (pinfunction "SDA_3") (pintype "input"))
      (node (ref "U3") (pin "41") (pinfunction "PB5_41") (pintype "passive"))
    )
    (net (code "28") (name "/VCELL1") (class "Default")
      (node (ref "R5") (pin "2") (pinfunction "2_2") (pintype "passive"))
      (node (ref "R7") (pin "2") (pinfunction "2_2") (pintype "passive"))
      (node (ref "U3") (pin "11") (pinfunction "PA1_11") (pintype "passive"))
    )
    (net (code "29") (name "/VCELL2") (class "Default")
      (node (ref "R11") (pin "2") (pinfunction "2_2") (pintype "passive"))
      (node (ref "R13") (pin "2") (pinfunction "2_2") (pintype "passive"))
      (node (ref "U3") (pin "12") (pinfunction "PA2_12") (pintype "passive"))
    )
    (net (code "30") (name "/VCELL3") (class "Default")
      (node (ref "R18") (pin "2") (pinfunction "2_2") (pintype "passive"))
      (node (ref "R20") (pin "2") (pinfunction "2_2") (pintype "passive"))
      (node (ref "U3") (pin "13") (pinfunction "PA3_13") (pintype "passive"))
    )
    (net (code "31") (name "/VCELL4") (class "Default")
      (node (ref "R24") (pin "2") (pinfunction "2_2") (pintype "passive"))
      (node (ref "R26") (pin "2") (pinfunction "2_2") (pintype "passive"))
      (node (ref "U3") (pin "14") (pinfunction "PA4_14") (pintype "passive"))
    )
    (net (code "32") (name "BAT_IN") (class "Default")
      (node (ref "J2") (pin "1") (pinfunction "+_1") (pintype "power_in"))
      (node (ref "R29") (pin "1") (pinfunction "+_1") (pintype "passive"))
      (node (ref "R30") (pin "1") (pinfunction "+_1") (pintype "passive"))
      (node (ref "U5") (pin "3") (pinfunction "VIN+_3") (pintype "input"))
    )
    (net (code "33") (name "GND") (class "Default")
      (node (ref "C1") (pin "1") (pinfunction "1_1") (pintype "passive"))
      (node (ref "C10") (pin "2") (pinfunction "2_2") (pintype "passive"))
      (node (ref "C11") (pin "1") (pinfunction "1_1") (pintype "passive"))
      (node (ref "C12") (pin "1") (pinfunction "1_1") (pintype "passive"))
      (node (ref "C13") (pin "1") (pinfunction "1_1") (pintype "passive"))
      (node (ref "C14") (pin "1") (pinfunction "1_1") (pintype "passive"))
      (node (ref "C15") (pin "1") (pinfunction "1_1") (pintype "passive"))
      (node (ref "C16") (pin "1") (pinfunction "1_1") (pintype "passive"))
      (node (ref "C17") (pin "1") (pinfunction "1_1") (pintype "passive"))
      (node (ref "C18") (pin "1") (pinfunction "1_1") (pintype "passive"))
      (node (ref "C19") (pin "2") (pinfunction "2_2") (pintype "passive"))
      (node (ref "C2") (pin "1") (pinfunction "1_1") (pintype "passive"))
      (node (ref "C20") (pin "1") (pinfunction "1_1") (pintype "passive"))
      (node (ref "C21") (pin "1") (pinfunction "1_1") (pintype "passive"))
      (node (ref "C22") (pin "2") (pinfunction "2_2") (pintype "passive"))
      (node (ref "C3") (pin "1") (pinfunction "1_1") (pintype "passive"))
      (node (ref "C4") (pin "2") (pinfunction "2_2") (pintype "passive"))
      (node (ref "C5") (pin "2") (pinfunction "2_2") (pintype "passive"))
      (node (ref "C6") (pin "2") (pinfunction "2_2") (pintype "passive"))
      (node (ref "C7") (pin "1") (pinfunction "1_1") (pintype "passive"))
      (node (ref "C8") (pin "1") (pinfunction "1_1") (pintype "passive"))
      (node (ref "C9") (pin "2") (pinfunction "2_2") (pintype "passive"))
      (node (ref "J2") (pin "2") (pinfunction "-_2") (pintype "power_in"))
      (node (ref "M1") (pin "3") (pinfunction "S_3") (pintype "passive"))
      (node (ref "M2") (pin "3") (pinfunction "S_3") (pintype "passive"))
      (node (ref "M3") (pin "3") (pinfunction "S_3") (pintype "passive"))
      (node (ref "M4") (pin "3") (pinfunction "S_3") (pintype "passive"))
      (node (ref "P1") (pin "1") (pinfunction "GND_1") (pintype "passive"))
      (node (ref "P2") (pin "7") (pinfunction "GND_7") (pintype "power_in"))
      (node (ref "P5") (pin "1") (pinfunction "1_1") (pintype "passive"))
      (node (ref "P7") (pin "2") (pinfunction "2_2") (pintype "passive"))
      (node (ref "P8") (pin "2") (pinfunction "2_2") (pintype "passive"))
      (node (ref "R13") (pin "1") (pinfunction "1_1") (pintype "passive"))
      (node (ref "R15") (pin "2") (pinfunction "2_2") (pintype "passive"))
      (node (ref "R20") (pin "1") (pinfunction "1_1") (pintype "passive"))
      (node (ref "R22") (pin "2") (pinfunction "2_2") (pintype "passive"))
      (node (ref "R26") (pin "1") (pinfunction "1_1") (pintype "passive"))
      (node (ref "R3") (pin "2") (pinfunction "2_2") (pintype "passive"))
      (node (ref "R32") (pin "2") (pinfunction "2_2") (pintype "passive"))
      (node (ref "R34") (pin "1") (pinfunction "1_1") (pintype "passive"))
      (node (ref "R36") (pin "2") (pinfunction "2_2") (pintype "passive"))
      (node (ref "R7") (pin "1") (pinfunction "1_1") (pintype "passive"))
      (node (ref "R9") (pin "2") (pinfunction "2_2") (pintype "passive"))
      (node (ref "SW1") (pin "2") (pinfunction "2_2") (pintype "passive"))
      (node (ref "U1") (pin "11") (pinfunction "VCC-_11") (pintype "power_in"))
      (node (ref "U2") (pin "1") (pinfunction "A0_1") (pintype "passive"))
      (node (ref "U2") (pin "2") (pinfunction "A1_2") (pintype "passive"))
      (node (ref "U2") (pin "3") (pinfunction "A2_3") (pintype "passive"))
      (node (ref "U2") (pin "4") (pinfunction "VSS_4") (pintype "passive"))
      (node (ref "U3") (pin "23") (pinfunction "VSS_23") (pintype "passive"))
      (node (ref "U3") (pin "47") (pinfunction "VSS_47") (pintype "passive"))
      (node (ref "U3") (pin "8") (pinfunction "VSSA_8") (pintype "passive"))
      (node (ref "U4") (pin "4") (pinfunction "VCC-_4") (pintype "power_in"))
      (node (ref "U5") (pin "2") (pinfunction "VCC-_2") (pintype "power_in"))
      (node (ref "U6") (pin "4") (pinfunction "VCC-_4") (pintype "power_in"))
    )
    (net (code "34") (name "Net-(C15-Pad2)") (class "Default")
      (node (ref "C15") (pin "2") (pinfunction "2_2") (pintype "passive"))
      (node (ref "R31") (pin "1") (pinfunction "1_1") (pintype "passive"))
    )
    (net (code "35") (name "Net-(C19-Pad1)") (class "Default")
      (node (ref "C19") (pin "1") (pinfunction "1_1") (pintype "passive"))
      (node (ref "R33") (pin "1") (pinfunction "1_1") (pintype "passive"))
    )
    (net (code "36") (name "Net-(C22-Pad1)") (class "Default")
      (node (ref "C22") (pin "1") (pinfunction "1_1") (pintype "passive"))
      (node (ref "R37") (pin "1") (pinfunction "1_1") (pintype "passive"))
    )
    (net (code "37") (name "Net-(J1--)") (class "Default")
      (node (ref "J1") (pin "2") (pinfunction "-_2") (pintype "power_in"))
      (node (ref "M1") (pin "2") (pinfunction "D_2") (pintype "passive"))
      (node (ref "M2") (pin "2") (pinfunction "D_2") (pintype "passive"))
      (node (ref "M3") (pin "2") (pinfunction "D_2") (pintype "passive"))
      (node (ref "M4") (pin "2") (pinfunction "D_2") (pintype "passive"))
    )
    (net (code "38") (name "Net-(M1-G)") (class "Default")
      (node (ref "M1") (pin "1") (pinfunction "G_1") (pintype "passive"))
      (node (ref "M2") (pin "1") (pinfunction "G_1") (pintype "passive"))
      (node (ref "M3") (pin "1") (pinfunction "G_1") (pintype "passive"))
      (node (ref "M4") (pin "1") (pinfunction "G_1") (pintype "passive"))
      (node (ref "R17") (pin "1") (pinfunction "1_1") (pintype "passive"))
    )
    (net (code "39") (name "Net-(U1A-1IN+)") (class "Default")
      (node (ref "R3") (pin "1") (pinfunction "1_1") (pintype "passive"))
      (node (ref "R4") (pin "2") (pinfunction "2_2") (pintype "passive"))
      (node (ref "U1") (pin "3") (pinfunction "1IN+_3") (pintype "input"))
    )
    (net (code "40") (name "Net-(U1A-1IN-)") (class "Default")
      (node (ref "R6") (pin "2") (pinfunction "2_2") (pintype "passive"))
      (node (ref "R8") (pin "1") (pinfunction "1_1") (pintype "passive"))
      (node (ref "U1") (pin "2") (pinfunction "1IN-_2") (pintype "input"))
    )
    (net (code "41") (name "Net-(U1A-1OUT)") (class "Default")
      (node (ref "R5") (pin "1") (pinfunction "1_1") (pintype "passive"))
      (node (ref "R8") (pin "2") (pinfunction "2_2") (pintype "passive"))
      (node (ref "U1") (pin "1") (pinfunction "1OUT_1") (pintype "output"))
    )
    (net (code "42") (name "Net-(U1B-2IN+)") (class "Default")
      (node (ref "R10") (pin "2") (pinfunction "2_2") (pintype "passive"))
      (node (ref "R9") (pin "1") (pinfunction "1_1") (pintype "passive"))
      (node (ref "U1") (pin "5") (pinfunction "2IN+_5") (pintype "input"))
    )
    (net (code "43") (name "Net-(U1B-2IN-)") (class "Default")
      (node (ref "R12") (pin "2") (pinfunction "2_2") (pintype "passive"))
      (node (ref "R14") (pin "1") (pinfunction "1_1") (pintype "passive"))
      (node (ref "U1") (pin "6") (pinfunction "2IN-_6") (pintype "input"))
    )
    (net (code "44") (name "Net-(U1B-2OUT)") (class "Default")
      (node (ref "R11") (pin "1") (pinfunction "1_1") (pintype "passive"))
      (node (ref "R14") (pin "2") (pinfunction "2_2") (pintype "passive"))
      (node (ref "U1") (pin "7") (pinfunction "2OUT_7") (pintype "output"))
    )
    (net (code "45") (name "Net-(U1C-3IN+)") (class "Default")
      (node (ref "R15") (pin "1") (pinfunction "1_1") (pintype "passive"))
      (node (ref "R16") (pin "2") (pinfunction "2_2") (pintype "passive"))
      (node (ref "U1") (pin "10") (pinfunction "3IN+_10") (pintype "input"))
    )
    (net (code "46") (name "Net-(U1C-3IN-)") (class "Default")
      (node (ref "R19") (pin "2") (pinfunction "2_2") (pintype "passive"))
      (node (ref "R21") (pin "1") (pinfunction "1_1") (pintype "passive"))
      (node (ref "U1") (pin "9") (pinfunction "3IN-_9") (pintype "input"))
    )
    (net (code "47") (name "Net-(U1C-3OUT)") (class "Default")
      (node (ref "R18") (pin "1") (pinfunction "1_1") (pintype "passive"))
      (node (ref "R21") (pin "2") (pinfunction "2_2") (pintype "passive"))
      (node (ref "U1") (pin "8") (pinfunction "3OUT_8") (pintype "output"))
    )
    (net (code "48") (name "Net-(U1D-4IN+)") (class "Default")
      (node (ref "R22") (pin "1") (pinfunction "1_1") (pintype "passive"))
      (node (ref "R23") (pin "2") (pinfunction "2_2") (pintype "passive"))
      (node (ref "U1") (pin "12") (pinfunction "4IN+_12") (pintype "input"))
    )
    (net (code "49") (name "Net-(U1D-4IN-)") (class "Default")
      (node (ref "R25") (pin "2") (pinfunction "2_2") (pintype "passive"))
      (node (ref "R28") (pin "1") (pinfunction "1_1") (pintype "passive"))
      (node (ref "U1") (pin "13") (pinfunction "4IN-_13") (pintype "input"))
    )
    (net (code "50") (name "Net-(U1D-4OUT)") (class "Default")
      (node (ref "R24") (pin "1") (pinfunction "1_1") (pintype "passive"))
      (node (ref "R28") (pin "2") (pinfunction "2_2") (pintype "passive"))
      (node (ref "U1") (pin "14") (pinfunction "4OUT_14") (pintype "output"))
    )
    (net (code "51") (name "Net-(U3-PF0-OSC_IN)") (class "Default")
      (node (ref "C7") (pin "2") (pinfunction "2_2") (pintype "passive"))
      (node (ref "U3") (pin "5") (pinfunction "PF0-OSC_IN_5") (pintype "passive"))
      (node (ref "X1") (pin "3") (pinfunction "9_3") (pintype "passive"))
    )
    (net (code "52") (name "Net-(U3-PF1-OSC_OUT)") (class "Default")
      (node (ref "C8") (pin "2") (pinfunction "2_2") (pintype "passive"))
      (node (ref "U3") (pin "6") (pinfunction "PF1-OSC_OUT_6") (pintype "passive"))
      (node (ref "X1") (pin "1") (pinfunction "8_1") (pintype "passive"))
    )
    (net (code "53") (name "Net-(U4A-1IN+)") (class "Default")
      (node (ref "P7") (pin "3") (pinfunction "3_3") (pintype "passive"))
      (node (ref "R33") (pin "2") (pinfunction "2_2") (pintype "passive"))
      (node (ref "U4") (pin "3") (pinfunction "1IN+_3") (pintype "input"))
    )
    (net (code "54") (name "Net-(U4A-1IN-)") (class "Default")
      (node (ref "R32") (pin "1") (pinfunction "1_1") (pintype "passive"))
      (node (ref "R35") (pin "1") (pinfunction "1_1") (pintype "passive"))
      (node (ref "U4") (pin "2") (pinfunction "1IN-_2") (pintype "input"))
    )
    (net (code "55") (name "Net-(U4B-2IN+)") (class "Default")
      (node (ref "P8") (pin "3") (pinfunction "3_3") (pintype "passive"))
      (node (ref "R37") (pin "2") (pinfunction "2_2") (pintype "passive"))
      (node (ref "U4") (pin "5") (pinfunction "2IN+_5") (pintype "input"))
    )
    (net (code "56") (name "Net-(U4B-2IN-)") (class "Default")
      (node (ref "R36") (pin "1") (pinfunction "1_1") (pintype "passive"))
      (node (ref "R38") (pin "1") (pinfunction "1_1") (pintype "passive"))
      (node (ref "U4") (pin "6") (pinfunction "2IN-_6") (pintype "input"))
    )
    (net (code "57") (name "Net-(U5-OUT)") (class "Default")
      (node (ref "R34") (pin "2") (pinfunction "2_2") (pintype "passive"))
      (node (ref "U5") (pin "1") (pinfunction "OUT_1") (pintype "output"))
      (node (ref "U6") (pin "3") (pinfunction "1IN+_3") (pintype "input"))
    )
    (net (code "58") (name "unconnected-(H1-Pad1)") (class "Default")
      (node (ref "H1") (pin "1") (pinfunction "1_1") (pintype "passive"))
    )
    (net (code "59") (name "unconnected-(H2-Pad1)") (class "Default")
      (node (ref "H2") (pin "1") (pinfunction "1_1") (pintype "passive"))
    )
    (net (code "60") (name "unconnected-(H3-Pad1)") (class "Default")
      (node (ref "H3") (pin "1") (pinfunction "1_1") (pintype "passive"))
    )
    (net (code "61") (name "unconnected-(H4-Pad1)") (class "Default")
      (node (ref "H4") (pin "1") (pinfunction "1_1") (pintype "passive"))
    )
    (net (code "62") (name "unconnected-(R29-Pad1)") (class "Default")
      (node (ref "R29") (pin "1") (pinfunction "1_1") (pintype "passive"))
    )
    (net (code "63") (name "unconnected-(R29-Pad2)") (class "Default")
      (node (ref "R29") (pin "2") (pinfunction "2_2") (pintype "passive"))
    )
    (net (code "64") (name "unconnected-(R30-Pad1)") (class "Default")
      (node (ref "R30") (pin "1") (pinfunction "1_1") (pintype "passive"))
    )
    (net (code "65") (name "unconnected-(R30-Pad2)") (class "Default")
      (node (ref "R30") (pin "2") (pinfunction "2_2") (pintype "passive"))
    )
    (net (code "66") (name "unconnected-(U3-BOOT0-Pad44)") (class "Default")
      (node (ref "U3") (pin "44") (pinfunction "BOOT0_44") (pintype "passive"))
    )
    (net (code "67") (name "unconnected-(U3-PA0-Pad10)") (class "Default")
      (node (ref "U3") (pin "10") (pinfunction "PA0_10") (pintype "passive"))
    )
    (net (code "68") (name "unconnected-(U3-PA10-Pad31)") (class "Default")
      (node (ref "U3") (pin "31") (pinfunction "PA10_31") (pintype "passive"))
    )
    (net (code "69") (name "unconnected-(U3-PA12-Pad33)") (class "Default")
      (node (ref "U3") (pin "33") (pinfunction "PA12_33") (pintype "passive"))
    )
    (net (code "70") (name "unconnected-(U3-PB0-Pad18)") (class "Default")
      (node (ref "U3") (pin "18") (pinfunction "PB0_18") (pintype "passive"))
    )
    (net (code "71") (name "unconnected-(U3-PB1-Pad19)") (class "Default")
      (node (ref "U3") (pin "19") (pinfunction "PB1_19") (pintype "passive"))
    )
    (net (code "72") (name "unconnected-(U3-PB2-Pad20)") (class "Default")
      (node (ref "U3") (pin "20") (pinfunction "PB2_20") (pintype "passive"))
    )
    (net (code "73") (name "unconnected-(U3-PB10-Pad21)") (class "Default")
      (node (ref "U3") (pin "21") (pinfunction "PB10_21") (pintype "passive"))
    )
    (net (code "74") (name "unconnected-(U3-PB12-Pad25)") (class "Default")
      (node (ref "U3") (pin "25") (pinfunction "PB12_25") (pintype "passive"))
    )
    (net (code "75") (name "unconnected-(U3-PB13-Pad26)") (class "Default")
      (node (ref "U3") (pin "26") (pinfunction "PB13_26") (pintype "passive"))
    )
    (net (code "76") (name "unconnected-(U3-PB14-Pad27)") (class "Default")
      (node (ref "U3") (pin "27") (pinfunction "PB14_27") (pintype "passive"))
    )
    (net (code "77") (name "unconnected-(U3-PC13-Pad2)") (class "Default")
      (node (ref "U3") (pin "2") (pinfunction "PC13_2") (pintype "passive"))
    )
    (net (code "78") (name "unconnected-(U3-PC14-OSC32_IN-Pad3)") (class "Default")
      (node (ref "U3") (pin "3") (pinfunction "PC14-OSC32_IN_3") (pintype "passive"))
    )
    (net (code "79") (name "unconnected-(U3-PC15-OSC32_OUT-Pad4)") (class "Default")
      (node (ref "U3") (pin "4") (pinfunction "PC15-OSC32_OUT_4") (pintype "passive"))
    )
    (net (code "80") (name "unconnected-(U3-PF6-Pad35)") (class "Default")
      (node (ref "U3") (pin "35") (pinfunction "PF6_35") (pintype "passive"))
    )
    (net (code "81") (name "unconnected-(U3-PF7-Pad36)") (class "Default")
      (node (ref "U3") (pin "36") (pinfunction "PF7_36") (pintype "passive"))
    )
  )
)
